# H2BR2.net
KiCad netlist of a schematic drawn in EAGLE
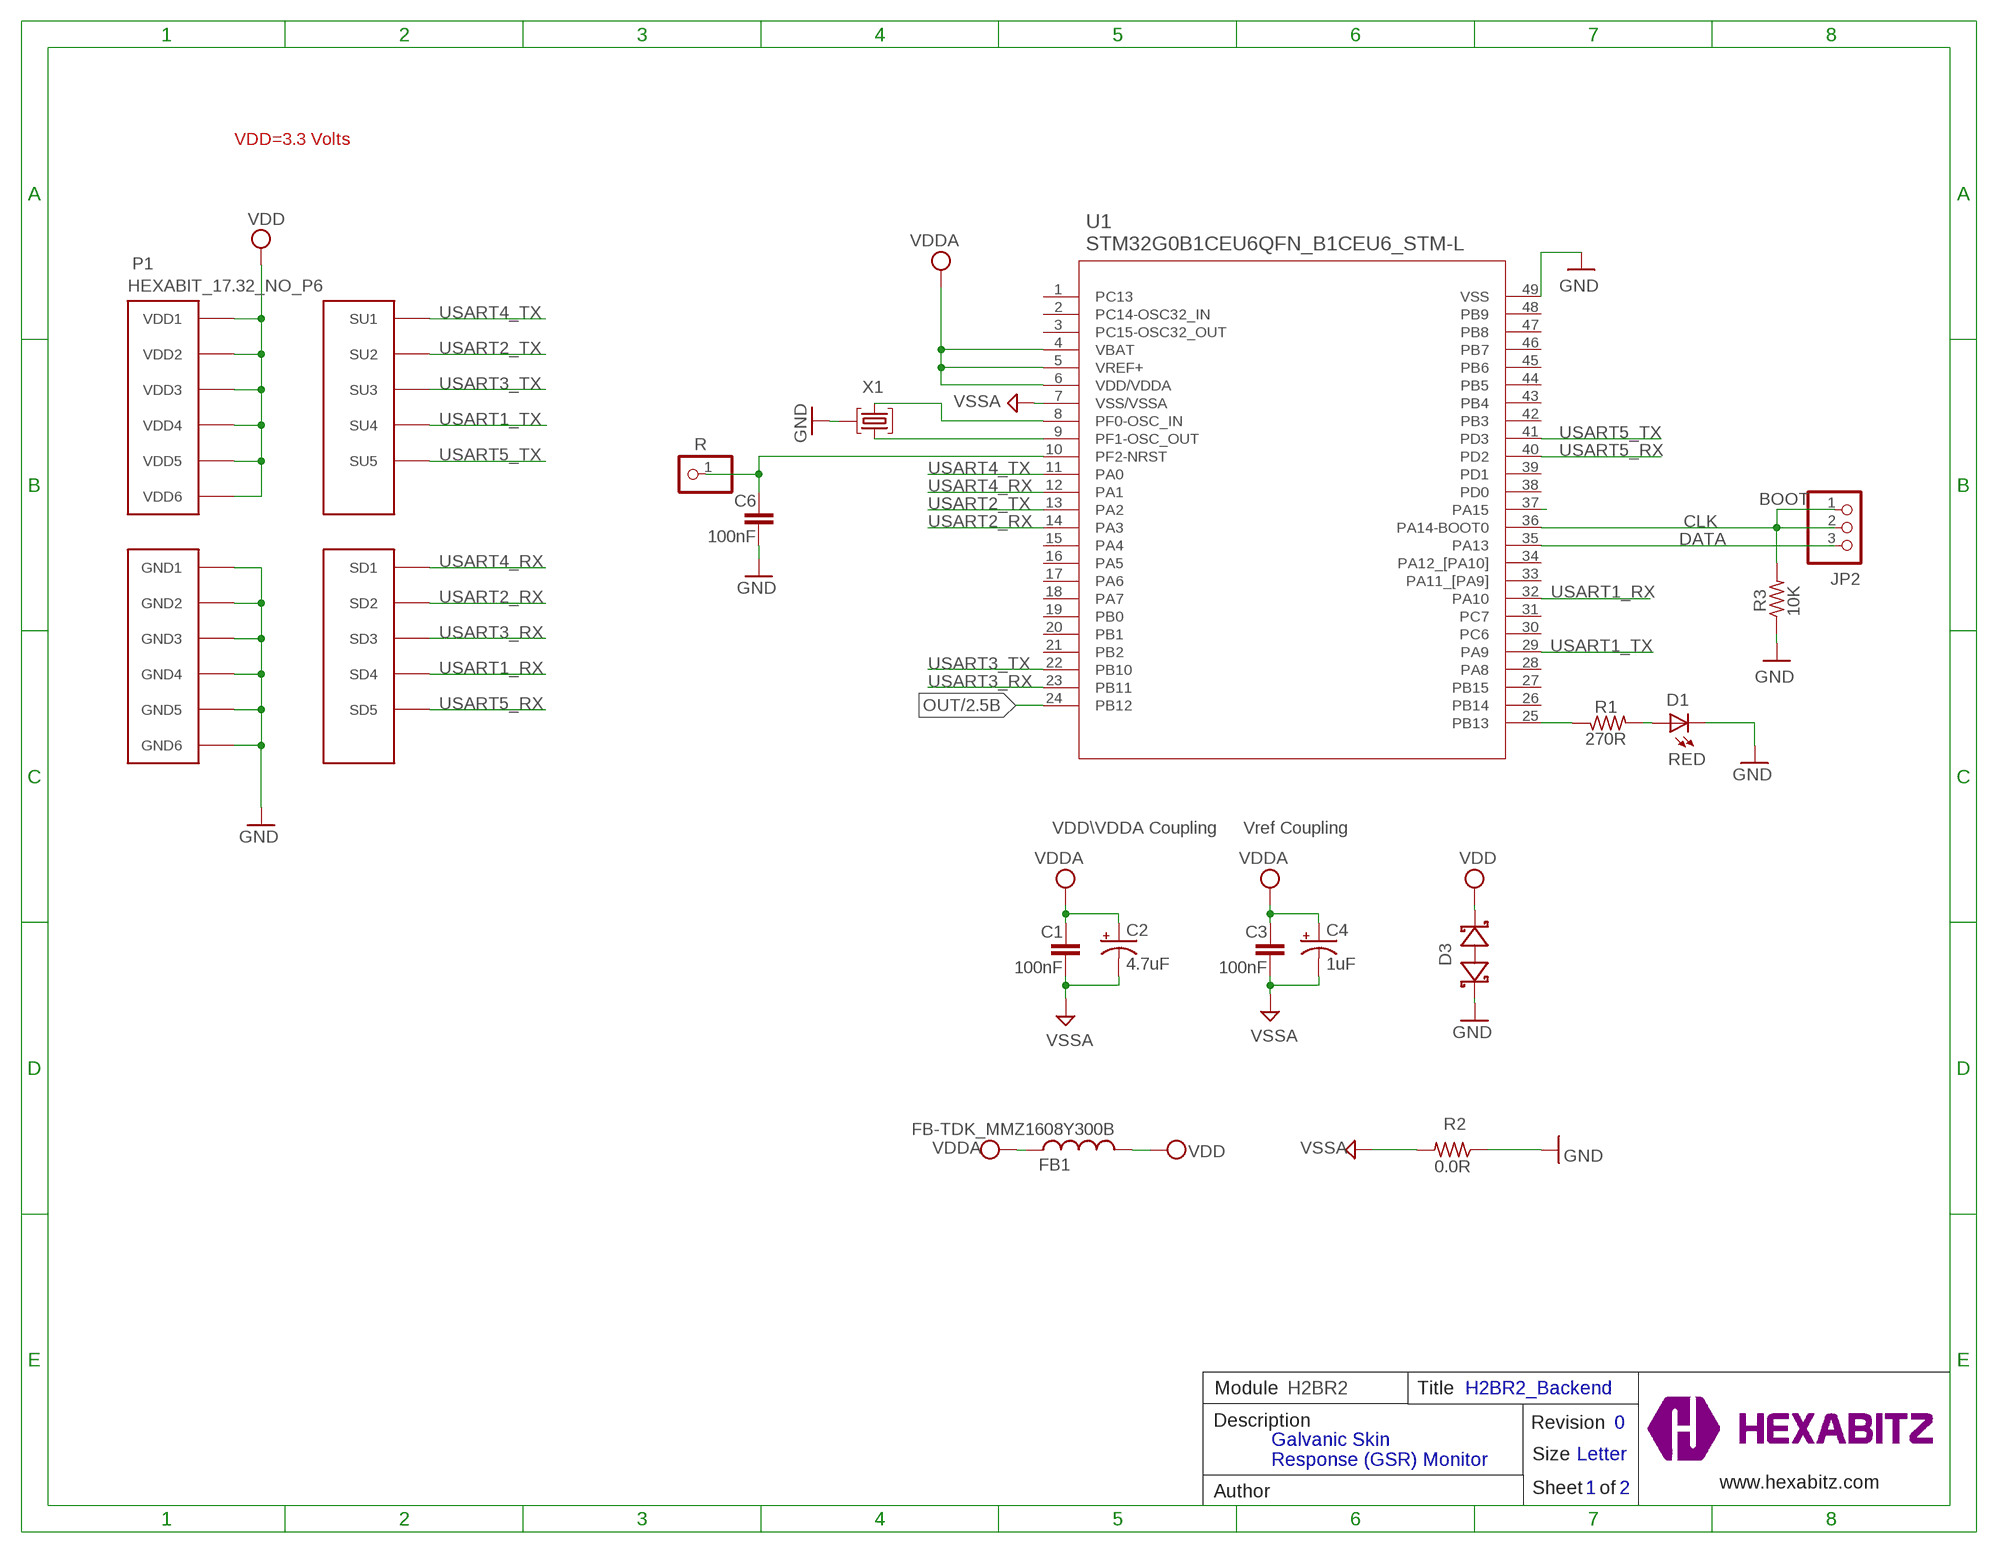
[diagram p0: schematic, sheet 1]
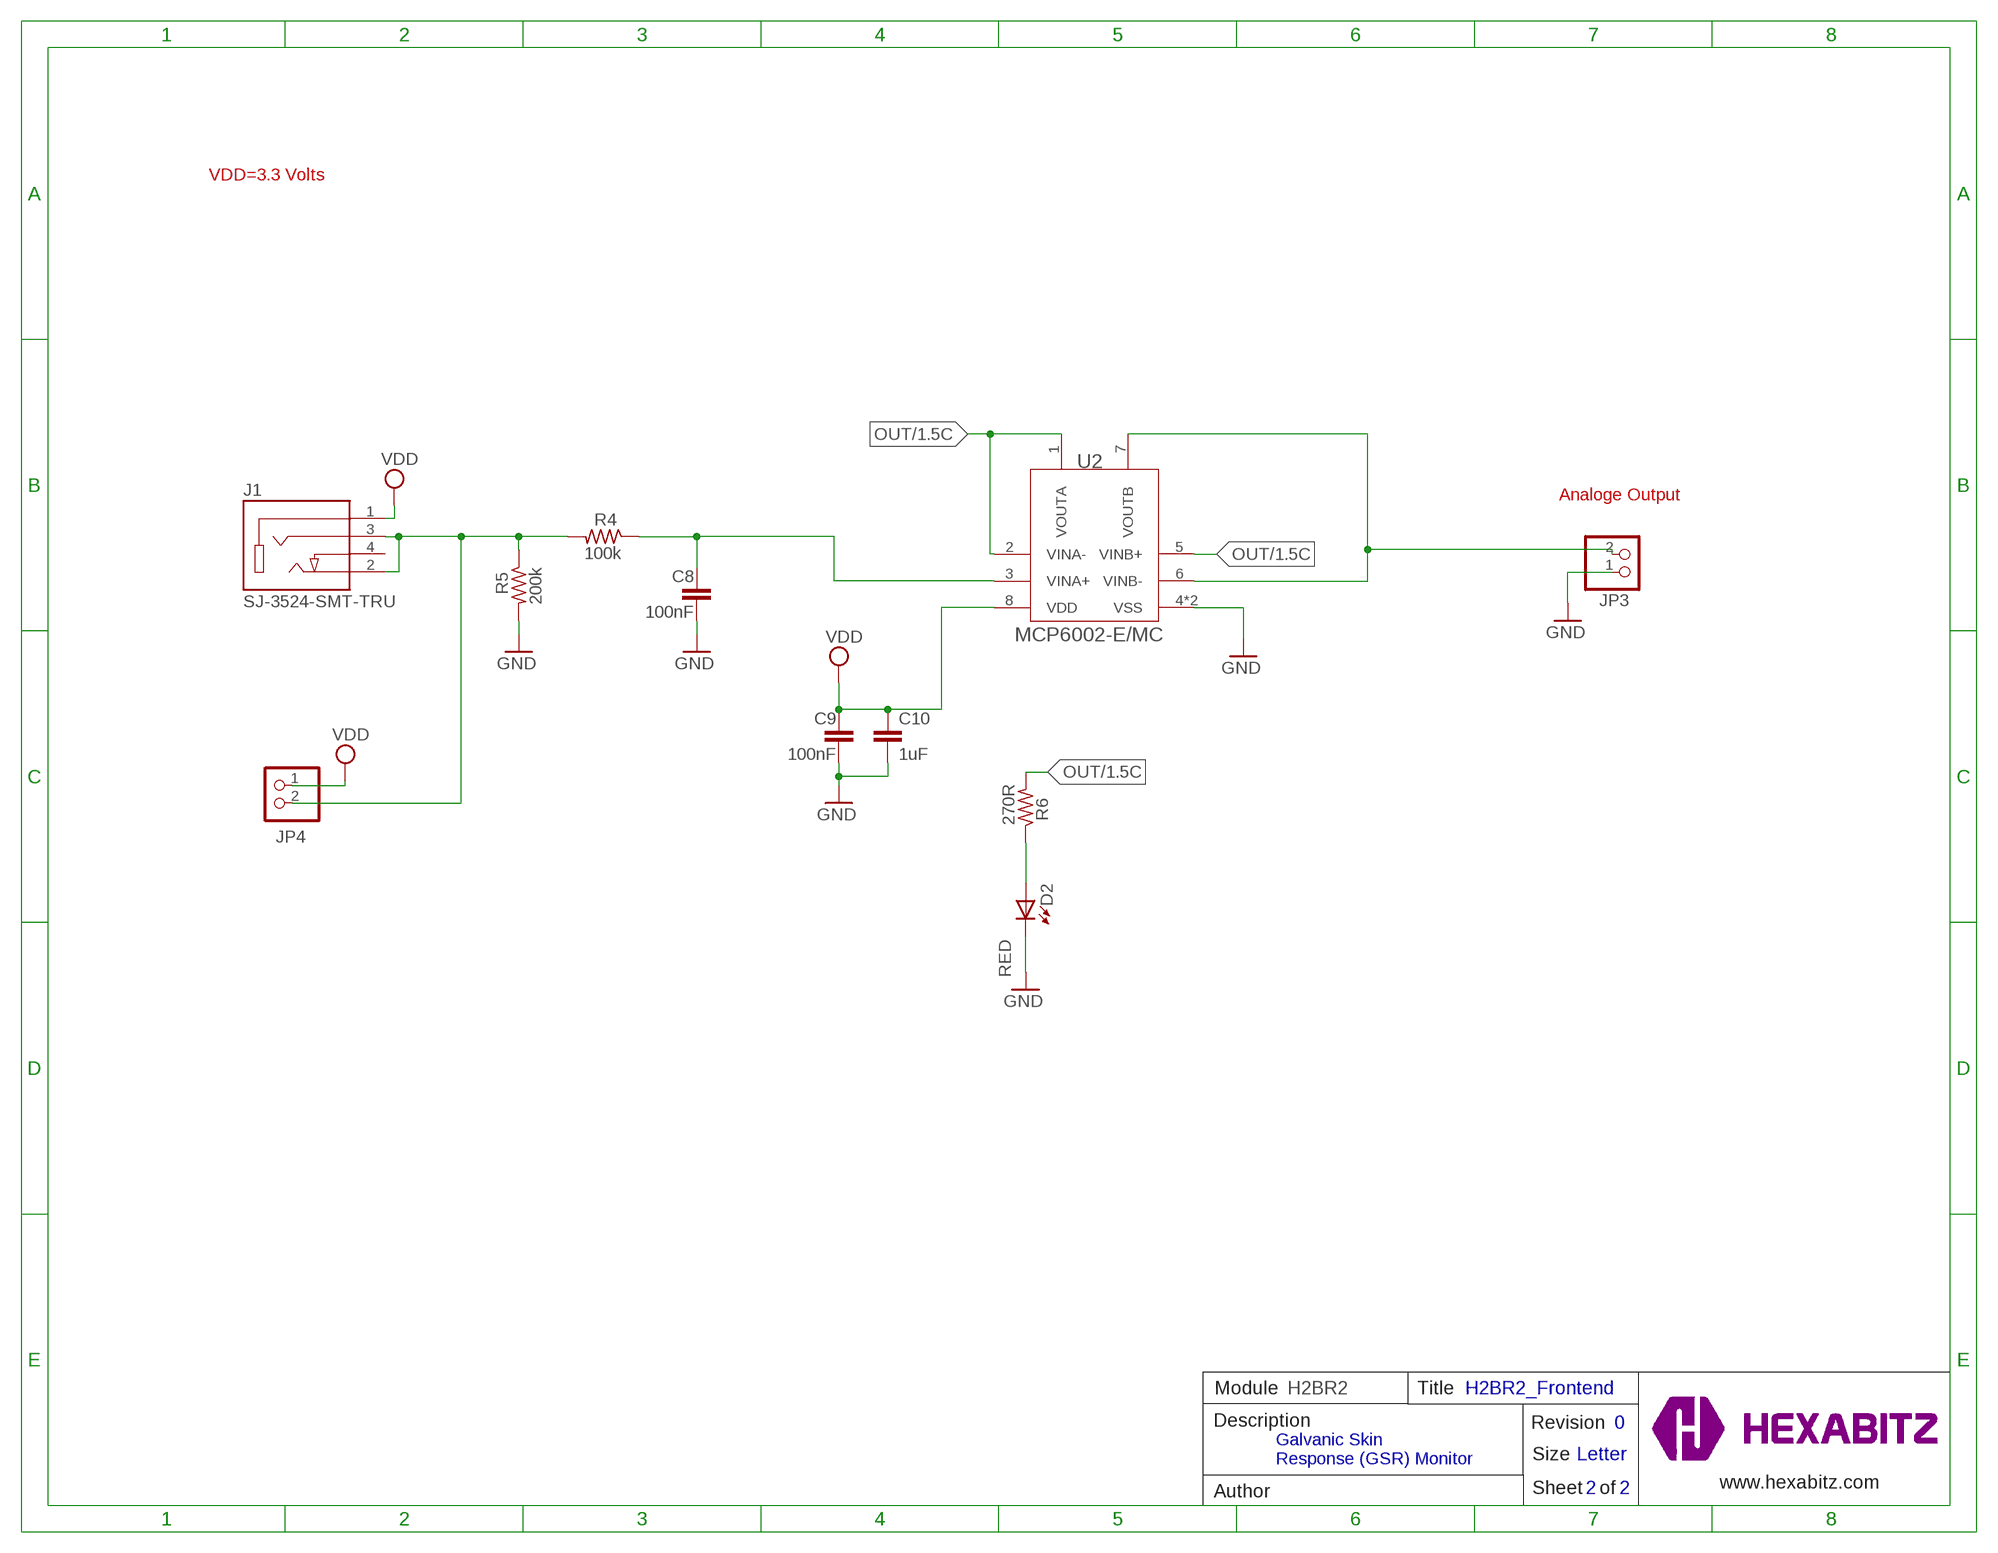
[diagram p1: schematic, sheet 2]

(export (version "E")
  (design (tool "Eeschema 10.0.6"))
  (components
    (comp (ref "C1")
      (value "100nF")
      (footprint "eagle-import:C-0603")
      (libsource (lib "eagle-import") (part "C-0603"))
    )
    (comp (ref "C2")
      (value "4.7uF")
      (footprint "eagle-import:C-0805-POL")
      (libsource (lib "eagle-import") (part "C-0805-POL"))
    )
    (comp (ref "C3")
      (value "100nF")
      (footprint "eagle-import:C-0603")
      (libsource (lib "eagle-import") (part "C-0603"))
    )
    (comp (ref "C4")
      (value "1uF")
      (footprint "eagle-import:C-0805-POL")
      (libsource (lib "eagle-import") (part "C-0805-POL"))
    )
    (comp (ref "C6")
      (value "100nF")
      (footprint "eagle-import:C-0603")
      (libsource (lib "eagle-import") (part "C-0603"))
    )
    (comp (ref "D1")
      (value "RED")
      (footprint "eagle-import:VLMS1300-GS08")
      (fields
        (field (name "MPN") "VLMS1300-GS08")
        (field (name "MFN") "Vishay")
        (field (name "MPN_1") "VLMS1300-GS08")
        (field (name "OCTOPART_URL") "https://octopart.com/vlms1300-gs08-vishay-21709201?r=sp&s=_gcP4_q8T1SC6PJQPTQ9yA")
      )
      (libsource (lib "eagle-import") (part "VLMS1300-GS08"))
    )
    (comp (ref "D3")
      (value "BOURNS_CDSOD323-T03SCBOURNS_CDSOD323-T03SC_0_0")
      (footprint "eagle-import:BOURNS_CDSOD323-T03SC_0")
      (fields (field (name "MPN") "CDSOD323-T03SC"))
      (libsource (lib "eagle-import") (part "BOURNS_CDSOD323-T03SCBOURNS_CDSOD323-T03SC_0_0"))
    )
    (comp (ref "FB1")
      (value "FB-TDK_MMZ1608Y300B")
      (footprint "eagle-import:FB-0603")
      (fields
        (field (name "MFN") "TDK ")
        (field (name "MPN") "MMZ1608Y300B")
        (field (name "OCTOPART_URL") "https://octopart.com/mmz1608y300b-tdk-368280?r=sp&s=cd9_2ZEqQ9q9UNBuQgHAiA")
      )
      (libsource (lib "eagle-import") (part "FB-0603"))
    )
    (comp (ref "JP1")
      (value "R")
      (footprint "eagle-import:1X01")
      (fields (field (name "MPN") "87227-1"))
      (libsource (lib "eagle-import") (part "PINHD-1X1"))
    )
    (comp (ref "JP2")
      (value "PINHD-1X3")
      (footprint "eagle-import:1X03")
      (libsource (lib "eagle-import") (part "PINHD-1X3"))
    )
    (comp (ref "P1")
      (value "HEXABIT_17.32_NO_P6")
      (footprint "eagle-import:HEXABIT_17.32_NO_P6")
      (libsource (lib "eagle-import") (part "HEXABIT_?_NO_P617.32"))
    )
    (comp (ref "R1")
      (value "270R")
      (footprint "eagle-import:R-0603")
      (libsource (lib "eagle-import") (part "R-0603"))
    )
    (comp (ref "R2")
      (value "0.0R")
      (footprint "eagle-import:R-0603")
      (fields
        (field (name "MFN") "Yageo")
        (field (name "MPN") "RC0603JR-070RL")
        (field (name "OCTOPART_URL") "https://octopart.com/rc0603jr-070rl-yageo-1241539?r=sp&s=X2NteqRjRNWrnx42Y0aliA")
        (field (name "RESISTANCE") "0.0 Ohm")
      )
      (libsource (lib "eagle-import") (part "R-0603"))
    )
    (comp (ref "R3")
      (value "10K")
      (footprint "eagle-import:R-0603")
      (libsource (lib "eagle-import") (part "R-0603"))
    )
    (comp (ref "TRIMBLE-LOGO1")
      (value "HEXA-LOGO")
      (footprint "eagle-import:HEXA-LOGO")
      (libsource (lib "eagle-import") (part "HEXA-LOGO"))
    )
    (comp (ref "U1")
      (value "STM32G0B1CEU6QFN_B1CEU6_STM-L")
      (footprint "eagle-import:QFN_B1CEU6_STM-L")
      (fields
        (field (name "MANUFACTURER_PART_NUMBER") "STM32G0B1CEU6")
        (field (name "COPYRIGHT") "Copyright (C) 2021 Ultra Librarian. All rights reserved.")
      )
      (libsource (lib "eagle-import") (part "STM32G0B1CEU6QFN_B1CEU6_STM-L"))
    )
    (comp (ref "X1")
      (value "XTALL_CSTCE8M00G52")
      (footprint "eagle-import:XTALL_CSTCE8M00G52")
      (fields (field (name "MPN") "CSTCE8M00G52Z-R0"))
      (libsource (lib "eagle-import") (part "XTALL_CSTCE8M00G52"))
    )
    (comp (ref "C8")
      (value "100nF")
      (footprint "eagle-import:C-0603")
      (libsource (lib "eagle-import") (part "C-0603"))
    )
    (comp (ref "C9")
      (value "100nF")
      (footprint "eagle-import:C-0603")
      (libsource (lib "eagle-import") (part "C-0603"))
    )
    (comp (ref "C10")
      (value "1uF")
      (footprint "eagle-import:C-0805")
      (libsource (lib "eagle-import") (part "C-0805"))
    )
    (comp (ref "D2")
      (value "RED")
      (footprint "eagle-import:VLMS1300-GS08")
      (fields
        (field (name "MPN") "VLMS1300-GS08")
        (field (name "MFN") "Vishay")
        (field (name "MPN_1") "VLMS1300-GS08")
        (field (name "OCTOPART_URL") "https://octopart.com/vlms1300-gs08-vishay-21709201?r=sp&s=_gcP4_q8T1SC6PJQPTQ9yA")
      )
      (libsource (lib "eagle-import") (part "VLMS1300-GS08"))
    )
    (comp (ref "J1")
      (value "SJ-3524-SMT-TRU")
      (footprint "eagle-import:CUI_SJ-3524-SMT")
      (fields (field (name "MPN") "SJ-3524-SMT-TR"))
      (libsource (lib "eagle-import") (part "SJ-3524-SMT-TRU"))
    )
    (comp (ref "JP3")
      (value "PINHD-1X2(ROUND)")
      (footprint "eagle-import:1X02")
      (libsource (lib "eagle-import") (part "PINHD-1X2(ROUND)"))
    )
    (comp (ref "JP4")
      (value "PINHD-1X2(ROUND)")
      (footprint "eagle-import:1X02")
      (libsource (lib "eagle-import") (part "PINHD-1X2(ROUND)"))
    )
    (comp (ref "R4")
      (value "100k")
      (footprint "eagle-import:R-0603")
      (libsource (lib "eagle-import") (part "R-0603"))
    )
    (comp (ref "R5")
      (value "200k")
      (footprint "eagle-import:R-0603")
      (libsource (lib "eagle-import") (part "R-0603"))
    )
    (comp (ref "R6")
      (value "270R")
      (footprint "eagle-import:R-0603")
      (libsource (lib "eagle-import") (part "R-0603"))
    )
    (comp (ref "U2")
      (value "MCP6002-E/MC")
      (footprint "eagle-import:SON50P200X300X100-9N")
      (libsource (lib "eagle-import") (part "MCP6002-E/MC"))
    )
  )
  (nets
    (net (code "1") (name "CLK") (class "Default")
      (node (ref "JP2") (pin "1") (pinfunction "1_1") (pintype "passive"))
      (node (ref "JP2") (pin "2") (pinfunction "2_2") (pintype "passive"))
      (node (ref "R3") (pin "2") (pinfunction "2_2") (pintype "passive"))
      (node (ref "U1") (pin "36") (pinfunction "PA14-BOOT0_36") (pintype "bidirectional"))
    )
    (net (code "2") (name "DATA") (class "Default")
      (node (ref "JP2") (pin "3") (pinfunction "3_3") (pintype "passive"))
      (node (ref "U1") (pin "35") (pinfunction "PA13_35") (pintype "bidirectional"))
    )
    (net (code "3") (name "GND") (class "Default")
      (node (ref "C10") (pin "2") (pinfunction "2_2") (pintype "passive"))
      (node (ref "C6") (pin "2") (pinfunction "2_2") (pintype "passive"))
      (node (ref "C8") (pin "2") (pinfunction "2_2") (pintype "passive"))
      (node (ref "C9") (pin "2") (pinfunction "2_2") (pintype "passive"))
      (node (ref "D1") (pin "C") (pinfunction "C_C") (pintype "passive"))
      (node (ref "D2") (pin "C") (pinfunction "C_C") (pintype "passive"))
      (node (ref "D3") (pin "1") (pinfunction "A_1") (pintype "passive"))
      (node (ref "JP3") (pin "1") (pinfunction "1_1") (pintype "passive"))
      (node (ref "P1") (pin "PAD_PD10") (pinfunction "GND4_PAD_PD10") (pintype "power_in"))
      (node (ref "P1") (pin "PAD_PD11") (pinfunction "GND5_PAD_PD11") (pintype "power_in"))
      (node (ref "P1") (pin "PAD_PD12") (pinfunction "GND6_PAD_PD12") (pintype "power_in"))
      (node (ref "P1") (pin "PAD_PD7") (pinfunction "GND1_PAD_PD7") (pintype "power_in"))
      (node (ref "P1") (pin "PAD_PD8") (pinfunction "GND2_PAD_PD8") (pintype "power_in"))
      (node (ref "P1") (pin "PAD_PD9") (pinfunction "GND3_PAD_PD9") (pintype "power_in"))
      (node (ref "R2") (pin "1") (pinfunction "1_1") (pintype "passive"))
      (node (ref "R3") (pin "1") (pinfunction "1_1") (pintype "passive"))
      (node (ref "R5") (pin "2") (pinfunction "2_2") (pintype "passive"))
      (node (ref "U1") (pin "49") (pinfunction "VSS_49") (pintype "passive"))
      (node (ref "U2") (pin "4") (pinfunction "VSS_4") (pintype "power_in"))
      (node (ref "U2") (pin "9") (pinfunction "VSS_9") (pintype "power_in"))
      (node (ref "X1") (pin "P$2") (pinfunction "2_P$2") (pintype "passive"))
    )
    (net (code "4") (name "Net-(D1-PadA)") (class "Default")
      (node (ref "D1") (pin "A") (pinfunction "A_A") (pintype "passive"))
      (node (ref "R1") (pin "2") (pinfunction "2_2") (pintype "passive"))
    )
    (net (code "5") (name "Net-(D2-PadA)") (class "Default")
      (node (ref "D2") (pin "A") (pinfunction "A_A") (pintype "passive"))
      (node (ref "R6") (pin "1") (pinfunction "1_1") (pintype "passive"))
    )
    (net (code "6") (name "Net-(J1-Pad2)") (class "Default")
      (node (ref "J1") (pin "2") (pinfunction "2_2") (pintype "passive"))
      (node (ref "J1") (pin "3") (pinfunction "3_3") (pintype "passive"))
      (node (ref "JP4") (pin "2") (pinfunction "2_2") (pintype "passive"))
      (node (ref "R4") (pin "2") (pinfunction "2_2") (pintype "passive"))
      (node (ref "R5") (pin "1") (pinfunction "1_1") (pintype "passive"))
    )
    (net (code "7") (name "Net-(U1-PB13)") (class "Default")
      (node (ref "R1") (pin "1") (pinfunction "1_1") (pintype "passive"))
      (node (ref "U1") (pin "25") (pinfunction "PB13_25") (pintype "bidirectional"))
    )
    (net (code "8") (name "Net-(U1-PF0-OSC_IN)") (class "Default")
      (node (ref "U1") (pin "8") (pinfunction "PF0-OSC_IN_8") (pintype "bidirectional"))
      (node (ref "X1") (pin "P$3") (pinfunction "3_P$3") (pintype "passive"))
    )
    (net (code "9") (name "Net-(U1-PF1-OSC_OUT)") (class "Default")
      (node (ref "U1") (pin "9") (pinfunction "PF1-OSC_OUT_9") (pintype "output"))
      (node (ref "X1") (pin "P$1") (pinfunction "1_P$1") (pintype "passive"))
    )
    (net (code "10") (name "Net-(U1-PF2-NRST)") (class "Default")
      (node (ref "C6") (pin "1") (pinfunction "1_1") (pintype "passive"))
      (node (ref "JP1") (pin "1") (pinfunction "1_1") (pintype "passive"))
      (node (ref "U1") (pin "10") (pinfunction "PF2-NRST_10") (pintype "bidirectional"))
    )
    (net (code "11") (name "Net-(U2-VINA+)") (class "Default")
      (node (ref "C8") (pin "1") (pinfunction "1_1") (pintype "passive"))
      (node (ref "R4") (pin "1") (pinfunction "1_1") (pintype "passive"))
      (node (ref "U2") (pin "3") (pinfunction "VINA+_3") (pintype "input"))
    )
    (net (code "12") (name "Net-(U2-VINB-)") (class "Default")
      (node (ref "JP3") (pin "2") (pinfunction "2_2") (pintype "passive"))
      (node (ref "U2") (pin "6") (pinfunction "VINB-_6") (pintype "input"))
      (node (ref "U2") (pin "7") (pinfunction "VOUTB_7") (pintype "output"))
    )
    (net (code "13") (name "OUT") (class "Default")
      (node (ref "R6") (pin "2") (pinfunction "2_2") (pintype "passive"))
      (node (ref "U1") (pin "24") (pinfunction "PB12_24") (pintype "bidirectional"))
      (node (ref "U2") (pin "1") (pinfunction "VOUTA_1") (pintype "output"))
      (node (ref "U2") (pin "2") (pinfunction "VINA-_2") (pintype "input"))
      (node (ref "U2") (pin "5") (pinfunction "VINB+_5") (pintype "input"))
    )
    (net (code "14") (name "USART1_RX") (class "Default")
      (node (ref "P1") (pin "PAD_PD4") (pinfunction "SD4_PAD_PD4") (pintype "bidirectional"))
      (node (ref "U1") (pin "32") (pinfunction "PA10_32") (pintype "bidirectional"))
    )
    (net (code "15") (name "USART1_TX") (class "Default")
      (node (ref "P1") (pin "PAD_PU4") (pinfunction "SU4_PAD_PU4") (pintype "bidirectional"))
      (node (ref "U1") (pin "29") (pinfunction "PA9_29") (pintype "bidirectional"))
    )
    (net (code "16") (name "USART2_RX") (class "Default")
      (node (ref "P1") (pin "PAD_PD2") (pinfunction "SD2_PAD_PD2") (pintype "bidirectional"))
      (node (ref "U1") (pin "14") (pinfunction "PA3_14") (pintype "bidirectional"))
    )
    (net (code "17") (name "USART2_TX") (class "Default")
      (node (ref "P1") (pin "PAD_PU2") (pinfunction "SU2_PAD_PU2") (pintype "bidirectional"))
      (node (ref "U1") (pin "13") (pinfunction "PA2_13") (pintype "bidirectional"))
    )
    (net (code "18") (name "USART3_RX") (class "Default")
      (node (ref "P1") (pin "PAD_PD3") (pinfunction "SD3_PAD_PD3") (pintype "bidirectional"))
      (node (ref "U1") (pin "23") (pinfunction "PB11_23") (pintype "bidirectional"))
    )
    (net (code "19") (name "USART3_TX") (class "Default")
      (node (ref "P1") (pin "PAD_PU3") (pinfunction "SU3_PAD_PU3") (pintype "bidirectional"))
      (node (ref "U1") (pin "22") (pinfunction "PB10_22") (pintype "bidirectional"))
    )
    (net (code "20") (name "USART4_RX") (class "Default")
      (node (ref "P1") (pin "PAD_PD1") (pinfunction "SD1_PAD_PD1") (pintype "bidirectional"))
      (node (ref "U1") (pin "12") (pinfunction "PA1_12") (pintype "bidirectional"))
    )
    (net (code "21") (name "USART4_TX") (class "Default")
      (node (ref "P1") (pin "PAD_PU1") (pinfunction "SU1_PAD_PU1") (pintype "bidirectional"))
      (node (ref "U1") (pin "11") (pinfunction "PA0_11") (pintype "bidirectional"))
    )
    (net (code "22") (name "USART5_RX") (class "Default")
      (node (ref "P1") (pin "PAD_PD5") (pinfunction "SD5_PAD_PD5") (pintype "bidirectional"))
      (node (ref "U1") (pin "40") (pinfunction "PD2_40") (pintype "bidirectional"))
    )
    (net (code "23") (name "USART5_TX") (class "Default")
      (node (ref "P1") (pin "PAD_PU5") (pinfunction "SU5_PAD_PU5") (pintype "bidirectional"))
      (node (ref "U1") (pin "41") (pinfunction "PD3_41") (pintype "bidirectional"))
    )
    (net (code "24") (name "VDD") (class "Default")
      (node (ref "C10") (pin "1") (pinfunction "1_1") (pintype "passive"))
      (node (ref "C9") (pin "1") (pinfunction "1_1") (pintype "passive"))
      (node (ref "D3") (pin "2") (pinfunction "C_2") (pintype "passive"))
      (node (ref "FB1") (pin "2") (pinfunction "2_2") (pintype "passive"))
      (node (ref "J1") (pin "1") (pinfunction "1_1") (pintype "passive"))
      (node (ref "JP4") (pin "1") (pinfunction "1_1") (pintype "passive"))
      (node (ref "P1") (pin "PAD_PU10") (pinfunction "VDD4_PAD_PU10") (pintype "power_in"))
      (node (ref "P1") (pin "PAD_PU11") (pinfunction "VDD5_PAD_PU11") (pintype "power_in"))
      (node (ref "P1") (pin "PAD_PU12") (pinfunction "VDD6_PAD_PU12") (pintype "power_in"))
      (node (ref "P1") (pin "PAD_PU7") (pinfunction "VDD1_PAD_PU7") (pintype "power_in"))
      (node (ref "P1") (pin "PAD_PU8") (pinfunction "VDD2_PAD_PU8") (pintype "power_in"))
      (node (ref "P1") (pin "PAD_PU9") (pinfunction "VDD3_PAD_PU9") (pintype "power_in"))
      (node (ref "U2") (pin "8") (pinfunction "VDD_8") (pintype "power_in"))
    )
    (net (code "25") (name "VDDA") (class "Default")
      (node (ref "C1") (pin "1") (pinfunction "1_1") (pintype "passive"))
      (node (ref "C2") (pin "1") (pinfunction "+_1") (pintype "passive"))
      (node (ref "C3") (pin "1") (pinfunction "1_1") (pintype "passive"))
      (node (ref "C4") (pin "1") (pinfunction "+_1") (pintype "passive"))
      (node (ref "FB1") (pin "1") (pinfunction "1_1") (pintype "passive"))
      (node (ref "U1") (pin "4") (pinfunction "VBAT_4") (pintype "passive"))
      (node (ref "U1") (pin "5") (pinfunction "VREF+_5") (pintype "power_in"))
      (node (ref "U1") (pin "6") (pinfunction "VDD/VDDA_6") (pintype "power_in"))
    )
    (net (code "26") (name "VSSA") (class "Default")
      (node (ref "C1") (pin "2") (pinfunction "2_2") (pintype "passive"))
      (node (ref "C2") (pin "2") (pinfunction "-_2") (pintype "passive"))
      (node (ref "C3") (pin "2") (pinfunction "2_2") (pintype "passive"))
      (node (ref "C4") (pin "2") (pinfunction "-_2") (pintype "passive"))
      (node (ref "R2") (pin "2") (pinfunction "2_2") (pintype "passive"))
      (node (ref "U1") (pin "7") (pinfunction "VSS/VSSA_7") (pintype "passive"))
    )
    (net (code "27") (name "unconnected-(J1-Pad4)") (class "Default")
      (node (ref "J1") (pin "4") (pinfunction "4_4") (pintype "passive"))
    )
    (net (code "28") (name "unconnected-(U1-PA4-Pad15)") (class "Default")
      (node (ref "U1") (pin "15") (pinfunction "PA4_15") (pintype "bidirectional"))
    )
    (net (code "29") (name "unconnected-(U1-PA5-Pad16)") (class "Default")
      (node (ref "U1") (pin "16") (pinfunction "PA5_16") (pintype "bidirectional"))
    )
    (net (code "30") (name "unconnected-(U1-PA6-Pad17)") (class "Default")
      (node (ref "U1") (pin "17") (pinfunction "PA6_17") (pintype "bidirectional"))
    )
    (net (code "31") (name "unconnected-(U1-PA7-Pad18)") (class "Default")
      (node (ref "U1") (pin "18") (pinfunction "PA7_18") (pintype "bidirectional"))
    )
    (net (code "32") (name "unconnected-(U1-PA8-Pad28)") (class "Default")
      (node (ref "U1") (pin "28") (pinfunction "PA8_28") (pintype "bidirectional"))
    )
    (net (code "33") (name "unconnected-(U1-PA11_[PA9]-Pad33)") (class "Default")
      (node (ref "U1") (pin "33") (pinfunction "PA11_[PA9]_33") (pintype "bidirectional"))
    )
    (net (code "34") (name "unconnected-(U1-PA12_[PA10]-Pad34)") (class "Default")
      (node (ref "U1") (pin "34") (pinfunction "PA12_[PA10]_34") (pintype "bidirectional"))
    )
    (net (code "35") (name "unconnected-(U1-PA15-Pad37)") (class "Default")
      (node (ref "U1") (pin "37") (pinfunction "PA15_37") (pintype "bidirectional"))
    )
    (net (code "36") (name "unconnected-(U1-PB0-Pad19)") (class "Default")
      (node (ref "U1") (pin "19") (pinfunction "PB0_19") (pintype "bidirectional"))
    )
    (net (code "37") (name "unconnected-(U1-PB1-Pad20)") (class "Default")
      (node (ref "U1") (pin "20") (pinfunction "PB1_20") (pintype "bidirectional"))
    )
    (net (code "38") (name "unconnected-(U1-PB2-Pad21)") (class "Default")
      (node (ref "U1") (pin "21") (pinfunction "PB2_21") (pintype "bidirectional"))
    )
    (net (code "39") (name "unconnected-(U1-PB3-Pad42)") (class "Default")
      (node (ref "U1") (pin "42") (pinfunction "PB3_42") (pintype "bidirectional"))
    )
    (net (code "40") (name "unconnected-(U1-PB4-Pad43)") (class "Default")
      (node (ref "U1") (pin "43") (pinfunction "PB4_43") (pintype "bidirectional"))
    )
    (net (code "41") (name "unconnected-(U1-PB5-Pad44)") (class "Default")
      (node (ref "U1") (pin "44") (pinfunction "PB5_44") (pintype "bidirectional"))
    )
    (net (code "42") (name "unconnected-(U1-PB6-Pad45)") (class "Default")
      (node (ref "U1") (pin "45") (pinfunction "PB6_45") (pintype "bidirectional"))
    )
    (net (code "43") (name "unconnected-(U1-PB7-Pad46)") (class "Default")
      (node (ref "U1") (pin "46") (pinfunction "PB7_46") (pintype "bidirectional"))
    )
    (net (code "44") (name "unconnected-(U1-PB8-Pad47)") (class "Default")
      (node (ref "U1") (pin "47") (pinfunction "PB8_47") (pintype "bidirectional"))
    )
    (net (code "45") (name "unconnected-(U1-PB9-Pad48)") (class "Default")
      (node (ref "U1") (pin "48") (pinfunction "PB9_48") (pintype "bidirectional"))
    )
    (net (code "46") (name "unconnected-(U1-PB14-Pad26)") (class "Default")
      (node (ref "U1") (pin "26") (pinfunction "PB14_26") (pintype "bidirectional"))
    )
    (net (code "47") (name "unconnected-(U1-PB15-Pad27)") (class "Default")
      (node (ref "U1") (pin "27") (pinfunction "PB15_27") (pintype "bidirectional"))
    )
    (net (code "48") (name "unconnected-(U1-PC6-Pad30)") (class "Default")
      (node (ref "U1") (pin "30") (pinfunction "PC6_30") (pintype "bidirectional"))
    )
    (net (code "49") (name "unconnected-(U1-PC7-Pad31)") (class "Default")
      (node (ref "U1") (pin "31") (pinfunction "PC7_31") (pintype "bidirectional"))
    )
    (net (code "50") (name "unconnected-(U1-PC13-Pad1)") (class "Default")
      (node (ref "U1") (pin "1") (pinfunction "PC13_1") (pintype "bidirectional"))
    )
    (net (code "51") (name "unconnected-(U1-PC14-OSC32_IN-Pad2)") (class "Default")
      (node (ref "U1") (pin "2") (pinfunction "PC14-OSC32_IN_2") (pintype "bidirectional"))
    )
    (net (code "52") (name "unconnected-(U1-PC15-OSC32_OUT-Pad3)") (class "Default")
      (node (ref "U1") (pin "3") (pinfunction "PC15-OSC32_OUT_3") (pintype "output"))
    )
    (net (code "53") (name "unconnected-(U1-PD0-Pad38)") (class "Default")
      (node (ref "U1") (pin "38") (pinfunction "PD0_38") (pintype "bidirectional"))
    )
    (net (code "54") (name "unconnected-(U1-PD1-Pad39)") (class "Default")
      (node (ref "U1") (pin "39") (pinfunction "PD1_39") (pintype "bidirectional"))
    )
  )
)
